# motor1.net
KiCad netlist of a schematic drawn in Altium Designer
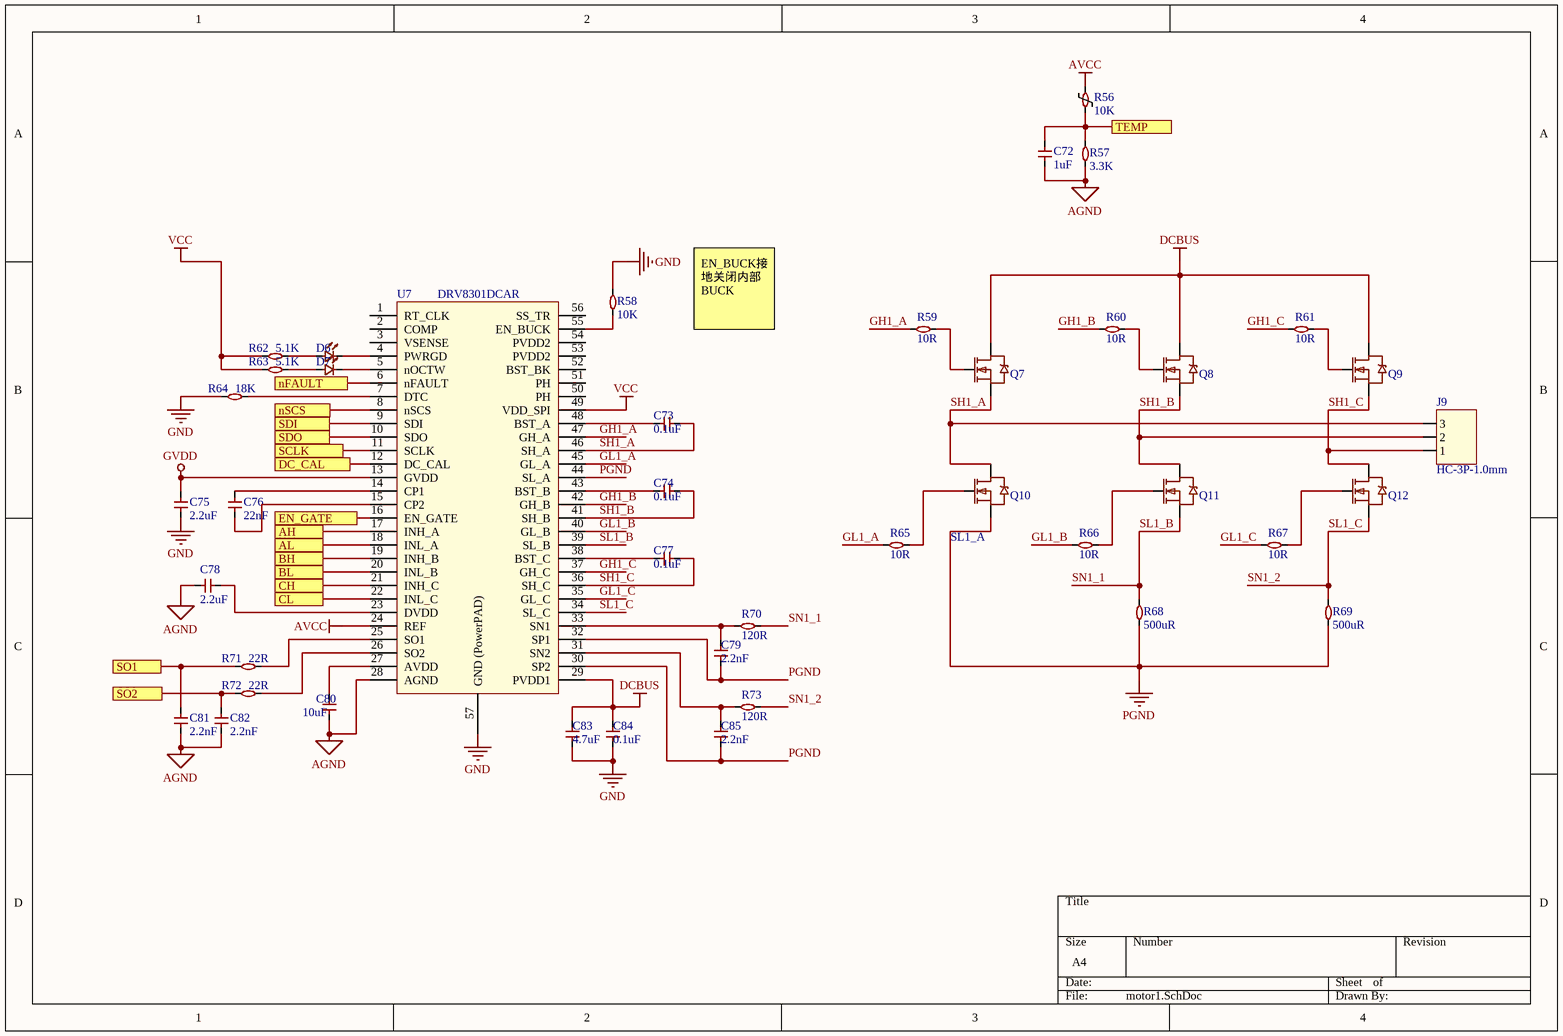
[diagram p0: motor1.SchDoc]

(export (version "E")
  (design (tool "Eeschema 10.0.6"))
  (components
    (comp (ref "C72")
      (value "1uF")
      (footprint "C0402")
      (description "贴片电容")
      (fields
        (field (name "MANUFACTURER") "SAMSUNG(三星)")
        (field (name "MANUFACTURER PART") "CL05A105KP5NNND")
      )
      (libsource (lib "schLibrary") (part "CAP"))
    )
    (comp (ref "C73")
      (value "0.1uF")
      (footprint "C0402")
      (description "贴片电容")
      (fields
        (field (name "MANUFACTURER") "SAMSUNG(三星)")
        (field (name "MANUFACTURER PART") "CL05A105KP5NNND")
      )
      (libsource (lib "schLibrary") (part "CAP"))
    )
    (comp (ref "C74")
      (value "0.1uF")
      (footprint "C0402")
      (description "贴片电容")
      (fields
        (field (name "MANUFACTURER") "SAMSUNG(三星)")
        (field (name "MANUFACTURER PART") "CL05A105KP5NNND")
      )
      (libsource (lib "schLibrary") (part "CAP"))
    )
    (comp (ref "C75")
      (value "2.2uF")
      (footprint "C0402")
      (description "贴片电容")
      (fields
        (field (name "MANUFACTURER") "SAMSUNG(三星)")
        (field (name "MANUFACTURER PART") "CL05A105KP5NNND")
      )
      (libsource (lib "schLibrary") (part "CAP"))
    )
    (comp (ref "C76")
      (value "22nF")
      (footprint "C0402")
      (description "贴片电容")
      (fields
        (field (name "MANUFACTURER") "SAMSUNG(三星)")
        (field (name "MANUFACTURER PART") "CL05A105KP5NNND")
      )
      (libsource (lib "schLibrary") (part "CAP"))
    )
    (comp (ref "C77")
      (value "0.1uF")
      (footprint "C0402")
      (description "贴片电容")
      (fields
        (field (name "MANUFACTURER") "SAMSUNG(三星)")
        (field (name "MANUFACTURER PART") "CL05A105KP5NNND")
      )
      (libsource (lib "schLibrary") (part "CAP"))
    )
    (comp (ref "C78")
      (value "2.2uF")
      (footprint "C0402")
      (description "贴片电容")
      (fields
        (field (name "MANUFACTURER") "SAMSUNG(三星)")
        (field (name "MANUFACTURER PART") "CL05A105KP5NNND")
      )
      (libsource (lib "schLibrary") (part "CAP"))
    )
    (comp (ref "C79")
      (value "2.2nF")
      (footprint "C0402")
      (description "贴片电容")
      (fields
        (field (name "MANUFACTURER") "SAMSUNG(三星)")
        (field (name "MANUFACTURER PART") "CL05A105KP5NNND")
      )
      (libsource (lib "schLibrary") (part "CAP"))
    )
    (comp (ref "C80")
      (value "10uF")
      (footprint "C0402")
      (description "贴片电容")
      (fields
        (field (name "MANUFACTURER") "SAMSUNG(三星)")
        (field (name "MANUFACTURER PART") "CL05A105KP5NNND")
      )
      (libsource (lib "schLibrary") (part "CAP"))
    )
    (comp (ref "C81")
      (value "2.2nF")
      (footprint "C0402")
      (description "贴片电容")
      (fields
        (field (name "MANUFACTURER") "SAMSUNG(三星)")
        (field (name "MANUFACTURER PART") "CL05A105KP5NNND")
      )
      (libsource (lib "schLibrary") (part "CAP"))
    )
    (comp (ref "C82")
      (value "2.2nF")
      (footprint "C0402")
      (description "贴片电容")
      (fields
        (field (name "MANUFACTURER") "SAMSUNG(三星)")
        (field (name "MANUFACTURER PART") "CL05A105KP5NNND")
      )
      (libsource (lib "schLibrary") (part "CAP"))
    )
    (comp (ref "C83")
      (value "4.7uF")
      (footprint "C0402")
      (description "贴片电容")
      (fields
        (field (name "MANUFACTURER") "SAMSUNG(三星)")
        (field (name "MANUFACTURER PART") "CL05A105KP5NNND")
      )
      (libsource (lib "schLibrary") (part "CAP"))
    )
    (comp (ref "C84")
      (value "0.1uF")
      (footprint "C0402")
      (description "贴片电容")
      (fields
        (field (name "MANUFACTURER") "SAMSUNG(三星)")
        (field (name "MANUFACTURER PART") "CL05A105KP5NNND")
      )
      (libsource (lib "schLibrary") (part "CAP"))
    )
    (comp (ref "C85")
      (value "2.2nF")
      (footprint "C0402")
      (description "贴片电容")
      (fields
        (field (name "MANUFACTURER") "SAMSUNG(三星)")
        (field (name "MANUFACTURER PART") "CL05A105KP5NNND")
      )
      (libsource (lib "schLibrary") (part "CAP"))
    )
    (comp (ref "D6")
      (value "LED")
      (footprint "LED-0402")
      (description "贴片发光二极管")
      (fields
        (field (name "MANUFACTURER") "SAMSUNG(三星)")
        (field (name "MANUFACTURER PART") "CL05A105KP5NNND")
      )
      (libsource (lib "schLibrary") (part "LED"))
    )
    (comp (ref "D7")
      (value "LED")
      (footprint "LED-0402")
      (description "贴片发光二极管")
      (fields
        (field (name "MANUFACTURER") "SAMSUNG(三星)")
        (field (name "MANUFACTURER PART") "CL05A105KP5NNND")
      )
      (libsource (lib "schLibrary") (part "LED"))
    )
    (comp (ref "J9")
      (value "HC-3P-1.0mm")
      (footprint "AMASS-MR30-M")
      (description "线对板连接器")
      (libsource (lib "schLibrary") (part "HC-3P-1.0mm"))
    )
    (comp (ref "Q7")
      (value "AP68N06G")
      (footprint "TDSON-8_L5.0-W6.0-3PIN")
      (description "N沟道功率mos管")
      (fields (field (name "MANUFACTURER") "BORN(伯恩半导体)") (field (name "MANUFACTURER PART") "AO3401A"))
      (libsource (lib "schLibrary") (part "NMOS"))
    )
    (comp (ref "Q8")
      (value "AP68N06G")
      (footprint "TDSON-8_L5.0-W6.0-3PIN")
      (description "N沟道功率mos管")
      (fields (field (name "MANUFACTURER") "BORN(伯恩半导体)") (field (name "MANUFACTURER PART") "AO3401A"))
      (libsource (lib "schLibrary") (part "NMOS"))
    )
    (comp (ref "Q9")
      (value "AP68N06G")
      (footprint "TDSON-8_L5.0-W6.0-3PIN")
      (description "N沟道功率mos管")
      (fields (field (name "MANUFACTURER") "BORN(伯恩半导体)") (field (name "MANUFACTURER PART") "AO3401A"))
      (libsource (lib "schLibrary") (part "NMOS"))
    )
    (comp (ref "Q10")
      (value "AP68N06G")
      (footprint "TDSON-8_L5.0-W6.0-3PIN")
      (description "N沟道功率mos管")
      (fields (field (name "MANUFACTURER") "BORN(伯恩半导体)") (field (name "MANUFACTURER PART") "AO3401A"))
      (libsource (lib "schLibrary") (part "NMOS"))
    )
    (comp (ref "Q11")
      (value "AP68N06G")
      (footprint "TDSON-8_L5.0-W6.0-3PIN")
      (description "N沟道功率mos管")
      (fields (field (name "MANUFACTURER") "BORN(伯恩半导体)") (field (name "MANUFACTURER PART") "AO3401A"))
      (libsource (lib "schLibrary") (part "NMOS"))
    )
    (comp (ref "Q12")
      (value "AP68N06G")
      (footprint "TDSON-8_L5.0-W6.0-3PIN")
      (description "N沟道功率mos管")
      (fields (field (name "MANUFACTURER") "BORN(伯恩半导体)") (field (name "MANUFACTURER PART") "AO3401A"))
      (libsource (lib "schLibrary") (part "NMOS"))
    )
    (comp (ref "R56")
      (value "10K")
      (footprint "R0402")
      (description "热敏电阻")
      (fields
        (field (name "MANUFACTURER") "UNI-ROYAL(厚声)")
        (field (name "MANUFACTURER PART") "0402WGF1001TCE")
      )
      (libsource (lib "schLibrary") (part "NTC"))
    )
    (comp (ref "R57")
      (value "3.3K")
      (footprint "R0402")
      (description "贴片电阻")
      (fields
        (field (name "MANUFACTURER") "UNI-ROYAL(厚声)")
        (field (name "MANUFACTURER PART") "0402WGF1001TCE")
      )
      (libsource (lib "schLibrary") (part "RES"))
    )
    (comp (ref "R58")
      (value "10K")
      (footprint "R0402")
      (description "贴片电阻")
      (fields
        (field (name "MANUFACTURER") "UNI-ROYAL(厚声)")
        (field (name "MANUFACTURER PART") "0402WGF1001TCE")
      )
      (libsource (lib "schLibrary") (part "RES"))
    )
    (comp (ref "R59")
      (value "10R")
      (footprint "R0402")
      (description "贴片电阻")
      (fields
        (field (name "MANUFACTURER") "UNI-ROYAL(厚声)")
        (field (name "MANUFACTURER PART") "0402WGF1001TCE")
      )
      (libsource (lib "schLibrary") (part "RES"))
    )
    (comp (ref "R60")
      (value "10R")
      (footprint "R0402")
      (description "贴片电阻")
      (fields
        (field (name "MANUFACTURER") "UNI-ROYAL(厚声)")
        (field (name "MANUFACTURER PART") "0402WGF1001TCE")
      )
      (libsource (lib "schLibrary") (part "RES"))
    )
    (comp (ref "R61")
      (value "10R")
      (footprint "R0402")
      (description "贴片电阻")
      (fields
        (field (name "MANUFACTURER") "UNI-ROYAL(厚声)")
        (field (name "MANUFACTURER PART") "0402WGF1001TCE")
      )
      (libsource (lib "schLibrary") (part "RES"))
    )
    (comp (ref "R62")
      (value "5.1K")
      (footprint "R0402")
      (description "贴片电阻")
      (fields
        (field (name "MANUFACTURER") "UNI-ROYAL(厚声)")
        (field (name "MANUFACTURER PART") "0402WGF1001TCE")
      )
      (libsource (lib "schLibrary") (part "RES"))
    )
    (comp (ref "R63")
      (value "5.1K")
      (footprint "R0402")
      (description "贴片电阻")
      (fields
        (field (name "MANUFACTURER") "UNI-ROYAL(厚声)")
        (field (name "MANUFACTURER PART") "0402WGF1001TCE")
      )
      (libsource (lib "schLibrary") (part "RES"))
    )
    (comp (ref "R64")
      (value "18K")
      (footprint "R0402")
      (description "贴片电阻")
      (fields
        (field (name "MANUFACTURER") "UNI-ROYAL(厚声)")
        (field (name "MANUFACTURER PART") "0402WGF1001TCE")
      )
      (libsource (lib "schLibrary") (part "RES"))
    )
    (comp (ref "R65")
      (value "10R")
      (footprint "R0402")
      (description "贴片电阻")
      (fields
        (field (name "MANUFACTURER") "UNI-ROYAL(厚声)")
        (field (name "MANUFACTURER PART") "0402WGF1001TCE")
      )
      (libsource (lib "schLibrary") (part "RES"))
    )
    (comp (ref "R66")
      (value "10R")
      (footprint "R0402")
      (description "贴片电阻")
      (fields
        (field (name "MANUFACTURER") "UNI-ROYAL(厚声)")
        (field (name "MANUFACTURER PART") "0402WGF1001TCE")
      )
      (libsource (lib "schLibrary") (part "RES"))
    )
    (comp (ref "R67")
      (value "10R")
      (footprint "R0402")
      (description "贴片电阻")
      (fields
        (field (name "MANUFACTURER") "UNI-ROYAL(厚声)")
        (field (name "MANUFACTURER PART") "0402WGF1001TCE")
      )
      (libsource (lib "schLibrary") (part "RES"))
    )
    (comp (ref "R68")
      (value "500uR")
      (footprint "R2512")
      (description "贴片电阻")
      (fields
        (field (name "MANUFACTURER") "UNI-ROYAL(厚声)")
        (field (name "MANUFACTURER PART") "0402WGF1001TCE")
      )
      (libsource (lib "schLibrary") (part "RES"))
    )
    (comp (ref "R69")
      (value "500uR")
      (footprint "R2512")
      (description "贴片电阻")
      (fields
        (field (name "MANUFACTURER") "UNI-ROYAL(厚声)")
        (field (name "MANUFACTURER PART") "0402WGF1001TCE")
      )
      (libsource (lib "schLibrary") (part "RES"))
    )
    (comp (ref "R70")
      (value "120R")
      (footprint "R0402")
      (description "贴片电阻")
      (fields
        (field (name "MANUFACTURER") "UNI-ROYAL(厚声)")
        (field (name "MANUFACTURER PART") "0402WGF1001TCE")
      )
      (libsource (lib "schLibrary") (part "RES"))
    )
    (comp (ref "R71")
      (value "22R")
      (footprint "R0402")
      (description "贴片电阻")
      (fields
        (field (name "MANUFACTURER") "UNI-ROYAL(厚声)")
        (field (name "MANUFACTURER PART") "0402WGF1001TCE")
      )
      (libsource (lib "schLibrary") (part "RES"))
    )
    (comp (ref "R72")
      (value "22R")
      (footprint "R0402")
      (description "贴片电阻")
      (fields
        (field (name "MANUFACTURER") "UNI-ROYAL(厚声)")
        (field (name "MANUFACTURER PART") "0402WGF1001TCE")
      )
      (libsource (lib "schLibrary") (part "RES"))
    )
    (comp (ref "R73")
      (value "120R")
      (footprint "R0402")
      (description "贴片电阻")
      (fields
        (field (name "MANUFACTURER") "UNI-ROYAL(厚声)")
        (field (name "MANUFACTURER PART") "0402WGF1001TCE")
      )
      (libsource (lib "schLibrary") (part "RES"))
    )
    (comp (ref "U7")
      (value "DRV8301DCAR")
      (footprint "HTSSOP-56_L14.0-W6.0-P0.50")
      (description "三相电机/栅极驱动IC")
      (libsource (lib "schLibrary") (part "DRV8301DCAR"))
    )
  )
  (nets
    (net (code "1") (name "/AH") (class "Default")
      (node (ref "U7") (pin "17") (pinfunction "INH_A_17") (pintype "passive"))
    )
    (net (code "2") (name "/AL") (class "Default")
      (node (ref "U7") (pin "18") (pinfunction "INL_A_18") (pintype "passive"))
    )
    (net (code "3") (name "/BH") (class "Default")
      (node (ref "U7") (pin "19") (pinfunction "INH_B_19") (pintype "passive"))
    )
    (net (code "4") (name "/BL") (class "Default")
      (node (ref "U7") (pin "20") (pinfunction "INL_B_20") (pintype "passive"))
    )
    (net (code "5") (name "/CH") (class "Default")
      (node (ref "U7") (pin "21") (pinfunction "INH_C_21") (pintype "passive"))
    )
    (net (code "6") (name "/CL") (class "Default")
      (node (ref "U7") (pin "22") (pinfunction "INL_C_22") (pintype "passive"))
    )
    (net (code "7") (name "/DC_CAL") (class "Default")
      (node (ref "U7") (pin "12") (pinfunction "DC_CAL_12") (pintype "passive"))
    )
    (net (code "8") (name "/EN_GATE") (class "Default")
      (node (ref "U7") (pin "16") (pinfunction "EN_GATE_16") (pintype "passive"))
    )
    (net (code "9") (name "/GH1_A") (class "Default")
      (node (ref "R59") (pin "2") (pinfunction "2_2") (pintype "passive"))
      (node (ref "U7") (pin "47") (pinfunction "GH_A_47") (pintype "passive"))
    )
    (net (code "10") (name "/GH1_B") (class "Default")
      (node (ref "R60") (pin "2") (pinfunction "2_2") (pintype "passive"))
      (node (ref "U7") (pin "42") (pinfunction "GH_B_42") (pintype "passive"))
    )
    (net (code "11") (name "/GH1_C") (class "Default")
      (node (ref "R61") (pin "2") (pinfunction "2_2") (pintype "passive"))
      (node (ref "U7") (pin "37") (pinfunction "GH_C_37") (pintype "passive"))
    )
    (net (code "12") (name "/GL1_A") (class "Default")
      (node (ref "R65") (pin "2") (pinfunction "2_2") (pintype "passive"))
      (node (ref "U7") (pin "45") (pinfunction "GL_A_45") (pintype "passive"))
    )
    (net (code "13") (name "/GL1_B") (class "Default")
      (node (ref "R66") (pin "2") (pinfunction "2_2") (pintype "passive"))
      (node (ref "U7") (pin "40") (pinfunction "GL_B_40") (pintype "passive"))
    )
    (net (code "14") (name "/GL1_C") (class "Default")
      (node (ref "R67") (pin "2") (pinfunction "2_2") (pintype "passive"))
      (node (ref "U7") (pin "35") (pinfunction "GL_C_35") (pintype "passive"))
    )
    (net (code "15") (name "/SCLK") (class "Default")
      (node (ref "U7") (pin "11") (pinfunction "SCLK_11") (pintype "passive"))
    )
    (net (code "16") (name "/SDI") (class "Default")
      (node (ref "U7") (pin "9") (pinfunction "SDI_9") (pintype "passive"))
    )
    (net (code "17") (name "/SDO") (class "Default")
      (node (ref "U7") (pin "10") (pinfunction "SDO_10") (pintype "passive"))
    )
    (net (code "18") (name "/SH1_A") (class "Default")
      (node (ref "C73") (pin "2") (pinfunction "2_2") (pintype "passive"))
      (node (ref "J9") (pin "3") (pinfunction "3_3") (pintype "passive"))
      (node (ref "Q10") (pin "3") (pinfunction "D_3") (pintype "passive"))
      (node (ref "Q7") (pin "2") (pinfunction "S_2") (pintype "passive"))
      (node (ref "U7") (pin "46") (pinfunction "SH_A_46") (pintype "passive"))
    )
    (net (code "19") (name "/SH1_B") (class "Default")
      (node (ref "C74") (pin "2") (pinfunction "2_2") (pintype "passive"))
      (node (ref "J9") (pin "2") (pinfunction "2_2") (pintype "passive"))
      (node (ref "Q11") (pin "3") (pinfunction "D_3") (pintype "passive"))
      (node (ref "Q8") (pin "2") (pinfunction "S_2") (pintype "passive"))
      (node (ref "U7") (pin "41") (pinfunction "SH_B_41") (pintype "passive"))
    )
    (net (code "20") (name "/SH1_C") (class "Default")
      (node (ref "C77") (pin "2") (pinfunction "2_2") (pintype "passive"))
      (node (ref "J9") (pin "1") (pinfunction "1_1") (pintype "passive"))
      (node (ref "Q12") (pin "3") (pinfunction "D_3") (pintype "passive"))
      (node (ref "Q9") (pin "2") (pinfunction "S_2") (pintype "passive"))
      (node (ref "U7") (pin "36") (pinfunction "SH_C_36") (pintype "passive"))
    )
    (net (code "21") (name "/SL1_B") (class "Default")
      (node (ref "Q11") (pin "2") (pinfunction "S_2") (pintype "passive"))
      (node (ref "R68") (pin "1") (pinfunction "1_1") (pintype "passive"))
      (node (ref "R70") (pin "2") (pinfunction "2_2") (pintype "passive"))
      (node (ref "U7") (pin "39") (pinfunction "SL_B_39") (pintype "passive"))
    )
    (net (code "22") (name "/SL1_C") (class "Default")
      (node (ref "Q12") (pin "2") (pinfunction "S_2") (pintype "passive"))
      (node (ref "R69") (pin "1") (pinfunction "1_1") (pintype "passive"))
      (node (ref "R73") (pin "2") (pinfunction "2_2") (pintype "passive"))
      (node (ref "U7") (pin "34") (pinfunction "SL_C_34") (pintype "passive"))
    )
    (net (code "23") (name "/SO1") (class "Default")
      (node (ref "C81") (pin "1") (pinfunction "1_1") (pintype "passive"))
      (node (ref "R71") (pin "1") (pinfunction "1_1") (pintype "passive"))
    )
    (net (code "24") (name "/SO2") (class "Default")
      (node (ref "C82") (pin "1") (pinfunction "1_1") (pintype "passive"))
      (node (ref "R72") (pin "1") (pinfunction "1_1") (pintype "passive"))
    )
    (net (code "25") (name "/TEMP") (class "Default")
      (node (ref "C72") (pin "1") (pinfunction "1_1") (pintype "passive"))
      (node (ref "R56") (pin "1") (pinfunction "1_1") (pintype "passive"))
      (node (ref "R57") (pin "2") (pinfunction "2_2") (pintype "passive"))
    )
    (net (code "26") (name "/nFAULT") (class "Default")
      (node (ref "U7") (pin "6") (pinfunction "nFAULT_6") (pintype "passive"))
    )
    (net (code "27") (name "/nSCS") (class "Default")
      (node (ref "U7") (pin "8") (pinfunction "nSCS_8") (pintype "passive"))
    )
    (net (code "28") (name "AGND") (class "Default")
      (node (ref "C72") (pin "2") (pinfunction "2_2") (pintype "passive"))
      (node (ref "C78") (pin "1") (pinfunction "1_1") (pintype "passive"))
      (node (ref "C80") (pin "2") (pinfunction "2_2") (pintype "passive"))
      (node (ref "C81") (pin "2") (pinfunction "2_2") (pintype "passive"))
      (node (ref "C82") (pin "2") (pinfunction "2_2") (pintype "passive"))
      (node (ref "R57") (pin "1") (pinfunction "1_1") (pintype "passive"))
      (node (ref "U7") (pin "28") (pinfunction "AGND_28") (pintype "passive"))
    )
    (net (code "29") (name "AVCC") (class "Default")
      (node (ref "R56") (pin "2") (pinfunction "2_2") (pintype "passive"))
      (node (ref "U7") (pin "24") (pinfunction "REF_24") (pintype "passive"))
    )
    (net (code "30") (name "DCBUS") (class "Default")
      (node (ref "C83") (pin "1") (pinfunction "1_1") (pintype "passive"))
      (node (ref "C84") (pin "1") (pinfunction "1_1") (pintype "passive"))
      (node (ref "Q7") (pin "3") (pinfunction "D_3") (pintype "passive"))
      (node (ref "Q8") (pin "3") (pinfunction "D_3") (pintype "passive"))
      (node (ref "Q9") (pin "3") (pinfunction "D_3") (pintype "passive"))
      (node (ref "U7") (pin "29") (pinfunction "PVDD1_29") (pintype "passive"))
    )
    (net (code "31") (name "GND") (class "Default")
      (node (ref "C75") (pin "1") (pinfunction "1_1") (pintype "passive"))
      (node (ref "C83") (pin "2") (pinfunction "2_2") (pintype "passive"))
      (node (ref "C84") (pin "2") (pinfunction "2_2") (pintype "passive"))
      (node (ref "R58") (pin "2") (pinfunction "2_2") (pintype "passive"))
      (node (ref "R64") (pin "1") (pinfunction "1_1") (pintype "passive"))
      (node (ref "U7") (pin "57") (pinfunction "GND_(PowerPAD)_57") (pintype "passive"))
    )
    (net (code "32") (name "GVDD") (class "Default")
      (node (ref "C75") (pin "2") (pinfunction "2_2") (pintype "passive"))
      (node (ref "U7") (pin "13") (pinfunction "GVDD_13") (pintype "passive"))
    )
    (net (code "33") (name "Net-(D6-Pad2)") (class "Default")
      (node (ref "D6") (pin "2") (pinfunction "2_2") (pintype "passive"))
      (node (ref "R62") (pin "2") (pinfunction "2_2") (pintype "passive"))
    )
    (net (code "34") (name "Net-(D7-Pad2)") (class "Default")
      (node (ref "D7") (pin "2") (pinfunction "2_2") (pintype "passive"))
      (node (ref "R63") (pin "2") (pinfunction "2_2") (pintype "passive"))
    )
    (net (code "35") (name "Net-(Q7-G)") (class "Default")
      (node (ref "Q7") (pin "1") (pinfunction "G_1") (pintype "passive"))
      (node (ref "R59") (pin "1") (pinfunction "1_1") (pintype "passive"))
    )
    (net (code "36") (name "Net-(Q8-G)") (class "Default")
      (node (ref "Q8") (pin "1") (pinfunction "G_1") (pintype "passive"))
      (node (ref "R60") (pin "1") (pinfunction "1_1") (pintype "passive"))
    )
    (net (code "37") (name "Net-(Q9-G)") (class "Default")
      (node (ref "Q9") (pin "1") (pinfunction "G_1") (pintype "passive"))
      (node (ref "R61") (pin "1") (pinfunction "1_1") (pintype "passive"))
    )
    (net (code "38") (name "Net-(Q10-G)") (class "Default")
      (node (ref "Q10") (pin "1") (pinfunction "G_1") (pintype "passive"))
      (node (ref "R65") (pin "1") (pinfunction "1_1") (pintype "passive"))
    )
    (net (code "39") (name "Net-(Q11-G)") (class "Default")
      (node (ref "Q11") (pin "1") (pinfunction "G_1") (pintype "passive"))
      (node (ref "R66") (pin "1") (pinfunction "1_1") (pintype "passive"))
    )
    (net (code "40") (name "Net-(Q12-G)") (class "Default")
      (node (ref "Q12") (pin "1") (pinfunction "G_1") (pintype "passive"))
      (node (ref "R67") (pin "1") (pinfunction "1_1") (pintype "passive"))
    )
    (net (code "41") (name "Net-(U7-AVDD)") (class "Default")
      (node (ref "C80") (pin "1") (pinfunction "1_1") (pintype "passive"))
      (node (ref "U7") (pin "27") (pinfunction "AVDD_27") (pintype "passive"))
    )
    (net (code "42") (name "Net-(U7-BST_A)") (class "Default")
      (node (ref "C73") (pin "1") (pinfunction "1_1") (pintype "passive"))
      (node (ref "U7") (pin "48") (pinfunction "BST_A_48") (pintype "passive"))
    )
    (net (code "43") (name "Net-(U7-BST_B)") (class "Default")
      (node (ref "C74") (pin "1") (pinfunction "1_1") (pintype "passive"))
      (node (ref "U7") (pin "43") (pinfunction "BST_B_43") (pintype "passive"))
    )
    (net (code "44") (name "Net-(U7-BST_C)") (class "Default")
      (node (ref "C77") (pin "1") (pinfunction "1_1") (pintype "passive"))
      (node (ref "U7") (pin "38") (pinfunction "BST_C_38") (pintype "passive"))
    )
    (net (code "45") (name "Net-(U7-CP1)") (class "Default")
      (node (ref "C76") (pin "2") (pinfunction "2_2") (pintype "passive"))
      (node (ref "U7") (pin "14") (pinfunction "CP1_14") (pintype "passive"))
    )
    (net (code "46") (name "Net-(U7-CP2)") (class "Default")
      (node (ref "C76") (pin "1") (pinfunction "1_1") (pintype "passive"))
      (node (ref "U7") (pin "15") (pinfunction "CP2_15") (pintype "passive"))
    )
    (net (code "47") (name "Net-(U7-DTC)") (class "Default")
      (node (ref "R64") (pin "2") (pinfunction "2_2") (pintype "passive"))
      (node (ref "U7") (pin "7") (pinfunction "DTC_7") (pintype "passive"))
    )
    (net (code "48") (name "Net-(U7-DVDD)") (class "Default")
      (node (ref "C78") (pin "2") (pinfunction "2_2") (pintype "passive"))
      (node (ref "U7") (pin "23") (pinfunction "DVDD_23") (pintype "passive"))
    )
    (net (code "49") (name "Net-(U7-EN_BUCK)") (class "Default")
      (node (ref "R58") (pin "1") (pinfunction "1_1") (pintype "passive"))
      (node (ref "U7") (pin "55") (pinfunction "EN_BUCK_55") (pintype "passive"))
    )
    (net (code "50") (name "Net-(U7-PWRGD)") (class "Default")
      (node (ref "D6") (pin "1") (pinfunction "1_1") (pintype "passive"))
      (node (ref "U7") (pin "4") (pinfunction "PWRGD_4") (pintype "passive"))
    )
    (net (code "51") (name "Net-(U7-SN1)") (class "Default")
      (node (ref "C79") (pin "1") (pinfunction "1_1") (pintype "passive"))
      (node (ref "R70") (pin "1") (pinfunction "1_1") (pintype "passive"))
      (node (ref "U7") (pin "33") (pinfunction "SN1_33") (pintype "passive"))
    )
    (net (code "52") (name "Net-(U7-SN2)") (class "Default")
      (node (ref "C85") (pin "1") (pinfunction "1_1") (pintype "passive"))
      (node (ref "R73") (pin "1") (pinfunction "1_1") (pintype "passive"))
      (node (ref "U7") (pin "31") (pinfunction "SN2_31") (pintype "passive"))
    )
    (net (code "53") (name "Net-(U7-SO1)") (class "Default")
      (node (ref "R71") (pin "2") (pinfunction "2_2") (pintype "passive"))
      (node (ref "U7") (pin "25") (pinfunction "SO1_25") (pintype "passive"))
    )
    (net (code "54") (name "Net-(U7-SO2)") (class "Default")
      (node (ref "R72") (pin "2") (pinfunction "2_2") (pintype "passive"))
      (node (ref "U7") (pin "26") (pinfunction "SO2_26") (pintype "passive"))
    )
    (net (code "55") (name "Net-(U7-nOCTW)") (class "Default")
      (node (ref "D7") (pin "1") (pinfunction "1_1") (pintype "passive"))
      (node (ref "U7") (pin "5") (pinfunction "nOCTW_5") (pintype "passive"))
    )
    (net (code "56") (name "PGND") (class "Default")
      (node (ref "C79") (pin "2") (pinfunction "2_2") (pintype "passive"))
      (node (ref "C85") (pin "2") (pinfunction "2_2") (pintype "passive"))
      (node (ref "Q10") (pin "2") (pinfunction "S_2") (pintype "passive"))
      (node (ref "R68") (pin "2") (pinfunction "2_2") (pintype "passive"))
      (node (ref "R69") (pin "2") (pinfunction "2_2") (pintype "passive"))
      (node (ref "U7") (pin "30") (pinfunction "SP2_30") (pintype "passive"))
      (node (ref "U7") (pin "32") (pinfunction "SP1_32") (pintype "passive"))
      (node (ref "U7") (pin "44") (pinfunction "SL_A_44") (pintype "passive"))
    )
    (net (code "57") (name "VCC") (class "Default")
      (node (ref "R62") (pin "1") (pinfunction "1_1") (pintype "passive"))
      (node (ref "R63") (pin "1") (pinfunction "1_1") (pintype "passive"))
      (node (ref "U7") (pin "49") (pinfunction "VDD_SPI_49") (pintype "passive"))
    )
    (net (code "58") (name "unconnected-(U7-BST_BK-Pad52)") (class "Default")
      (node (ref "U7") (pin "52") (pinfunction "BST_BK_52") (pintype "passive"))
    )
    (net (code "59") (name "unconnected-(U7-COMP-Pad2)") (class "Default")
      (node (ref "U7") (pin "2") (pinfunction "COMP_2") (pintype "passive"))
    )
    (net (code "60") (name "unconnected-(U7-PH-Pad50)") (class "Default")
      (node (ref "U7") (pin "50") (pinfunction "PH_50") (pintype "passive"))
    )
    (net (code "61") (name "unconnected-(U7-PH-Pad51)") (class "Default")
      (node (ref "U7") (pin "51") (pinfunction "PH_51") (pintype "passive"))
    )
    (net (code "62") (name "unconnected-(U7-PVDD2-Pad53)") (class "Default")
      (node (ref "U7") (pin "53") (pinfunction "PVDD2_53") (pintype "passive"))
    )
    (net (code "63") (name "unconnected-(U7-PVDD2-Pad54)") (class "Default")
      (node (ref "U7") (pin "54") (pinfunction "PVDD2_54") (pintype "passive"))
    )
    (net (code "64") (name "unconnected-(U7-RT_CLK-Pad1)") (class "Default")
      (node (ref "U7") (pin "1") (pinfunction "RT_CLK_1") (pintype "passive"))
    )
    (net (code "65") (name "unconnected-(U7-SS_TR-Pad56)") (class "Default")
      (node (ref "U7") (pin "56") (pinfunction "SS_TR_56") (pintype "passive"))
    )
    (net (code "66") (name "unconnected-(U7-VSENSE-Pad3)") (class "Default")
      (node (ref "U7") (pin "3") (pinfunction "VSENSE_3") (pintype "passive"))
    )
  )
)
